# PX4FMUv2_4_6_8.net
KiCad netlist of a schematic drawn in Altium Designer
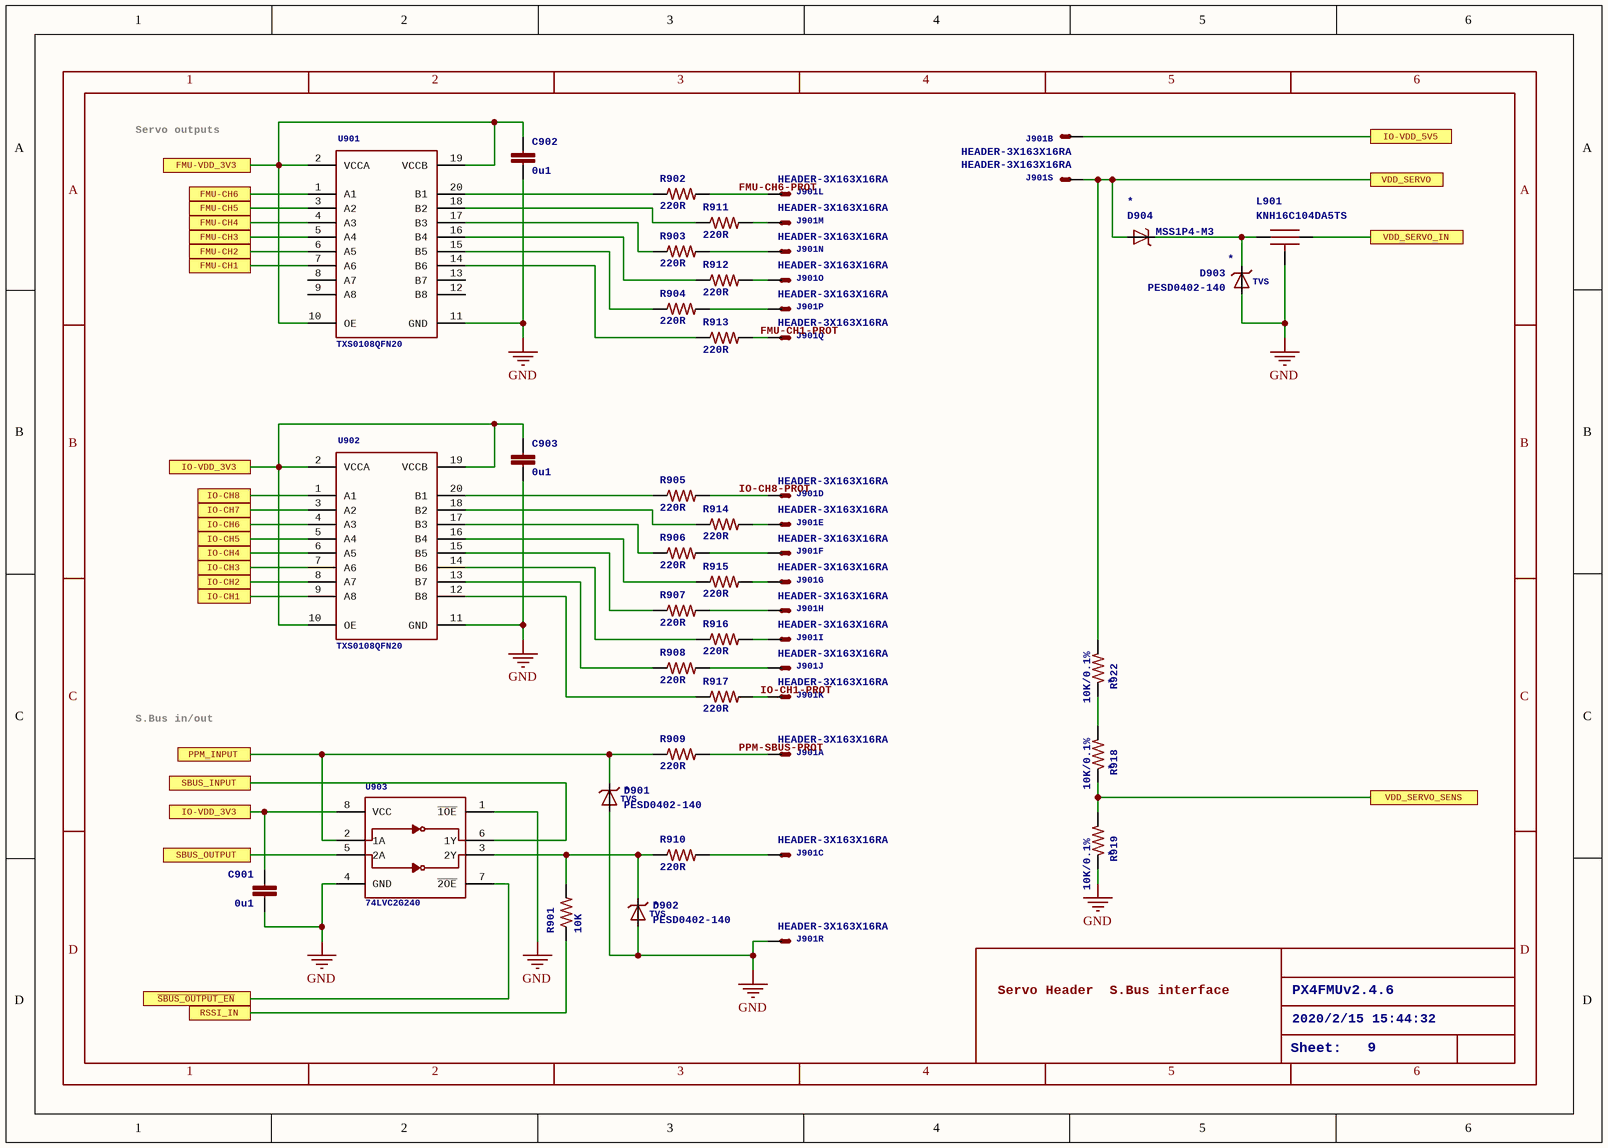
[diagram p0: PX4FMUv2.4.6_8.SchDoc]

(export (version "E")
  (design (tool "Eeschema 10.0.6"))
  (components
    (comp (ref "C901")
      (value "0u1")
      (footprint "0402-CAP")
      (description "CapacitorStandard 0603 ceramic capacitor, and 0.1\" leaded capacitor.")
      (fields (field (name "PARTNO") "CC0402ZRY5V7BB104"))
      (libsource (lib "") (part "CAP0402_1"))
    )
    (comp (ref "C902")
      (value "0u1")
      (footprint "0402-CAP")
      (description "CapacitorStandard 0603 ceramic capacitor, and 0.1\" leaded capacitor.")
      (fields (field (name "PARTNO") "CC0402ZRY5V7BB104"))
      (libsource (lib "pixhawk2") (part "CAP0402"))
    )
    (comp (ref "C903")
      (value "0u1")
      (footprint "0402-CAP")
      (description "CapacitorStandard 0603 ceramic capacitor, and 0.1\" leaded capacitor.")
      (fields (field (name "PARTNO") "CC0402ZRY5V7BB104"))
      (libsource (lib "pixhawk2") (part "CAP0402"))
    )
    (comp (ref "D901")
      (value "PESD0402-140")
      (footprint "0402-TVS")
      (fields (field (name "NAME") "*") (field (name "TVS") "TVS"))
      (libsource (lib "pixhawk2") (part "DIODE-TVS"))
    )
    (comp (ref "D902")
      (value "PESD0402-140")
      (footprint "0402-TVS")
      (fields (field (name "NAME") "*") (field (name "TVS") "TVS"))
      (libsource (lib "pixhawk2") (part "DIODE-TVS"))
    )
    (comp (ref "D903")
      (value "PESD0402-140")
      (footprint "0402-TVS")
      (fields (field (name "NAME") "*") (field (name "TVS") "TVS"))
      (libsource (lib "pixhawk2") (part "DIODE-TVS"))
    )
    (comp (ref "D904")
      (value "MSS1P4-M3")
      (footprint "MICROSMP")
      (description "Schottky barrier diode in DO214AC, e.g. Fairchild SS14.")
      (fields (field (name "NAME") "*") (field (name "PARTNO") "MSS1P4-M3/89A"))
      (libsource (lib "pixhawk2") (part "DIODE-SCHOTTKY_MSMP"))
    )
    (comp (ref "J901")
      (value "HEADER-3X163X16RA")
      (footprint "3X16RA")
      (description "3x16 servo header")
      (libsource (lib "pixhawk2") (part "HEADER-3X163X16RA"))
    )
    (comp (ref "L901")
      (value "KNH16C104DA5TS")
      (footprint "KYOCERA-KNH16-DA")
      (description "Kyocera KNH16C104DA5TS EMI filter")
      (libsource (lib "pixhawk2") (part "KNH16C104DA5TS"))
    )
    (comp (ref "R901")
      (value "10K")
      (footprint "0402-RES")
      (fields (field (name "PARTNO") "RC0402FR-0710KL"))
      (libsource (lib "pixhawk2") (part "RESISTOR0402-RES"))
    )
    (comp (ref "R902")
      (value "220R")
      (footprint "0402-RES")
      (fields (field (name "PARTNO") "RC0402FR-07220RL"))
      (libsource (lib "pixhawk2") (part "RESISTOR0402-RES"))
    )
    (comp (ref "R903")
      (value "220R")
      (footprint "0402-RES")
      (fields (field (name "PARTNO") "RC0402FR-07220RL"))
      (libsource (lib "pixhawk2") (part "RESISTOR0402-RES"))
    )
    (comp (ref "R904")
      (value "220R")
      (footprint "0402-RES")
      (fields (field (name "PARTNO") "RC0402FR-07220RL"))
      (libsource (lib "pixhawk2") (part "RESISTOR0402-RES"))
    )
    (comp (ref "R905")
      (value "220R")
      (footprint "0402-RES")
      (fields (field (name "PARTNO") "RC0402FR-07220RL"))
      (libsource (lib "pixhawk2") (part "RESISTOR0402-RES"))
    )
    (comp (ref "R906")
      (value "220R")
      (footprint "0402-RES")
      (fields (field (name "PARTNO") "RC0402FR-07220RL"))
      (libsource (lib "pixhawk2") (part "RESISTOR0402-RES"))
    )
    (comp (ref "R907")
      (value "220R")
      (footprint "0402-RES")
      (fields (field (name "PARTNO") "RC0402FR-07220RL"))
      (libsource (lib "pixhawk2") (part "RESISTOR0402-RES"))
    )
    (comp (ref "R908")
      (value "220R")
      (footprint "0402-RES")
      (fields (field (name "PARTNO") "RC0402FR-07220RL"))
      (libsource (lib "pixhawk2") (part "RESISTOR0402-RES"))
    )
    (comp (ref "R909")
      (value "220R")
      (footprint "0402-RES")
      (fields (field (name "PARTNO") "RC0402FR-07220RL"))
      (libsource (lib "pixhawk2") (part "RESISTOR0402-RES"))
    )
    (comp (ref "R910")
      (value "220R")
      (footprint "0402-RES")
      (fields (field (name "PARTNO") "RC0402FR-07220RL"))
      (libsource (lib "pixhawk2") (part "RESISTOR0402-RES"))
    )
    (comp (ref "R911")
      (value "220R")
      (footprint "0402-RES")
      (fields (field (name "PARTNO") "RC0402FR-07220RL"))
      (libsource (lib "pixhawk2") (part "RESISTOR0402-RES"))
    )
    (comp (ref "R912")
      (value "220R")
      (footprint "0402-RES")
      (fields (field (name "PARTNO") "RC0402FR-07220RL"))
      (libsource (lib "pixhawk2") (part "RESISTOR0402-RES"))
    )
    (comp (ref "R913")
      (value "220R")
      (footprint "0402-RES")
      (fields (field (name "PARTNO") "RC0402FR-07220RL"))
      (libsource (lib "pixhawk2") (part "RESISTOR0402-RES"))
    )
    (comp (ref "R914")
      (value "220R")
      (footprint "0402-RES")
      (fields (field (name "PARTNO") "RC0402FR-07220RL"))
      (libsource (lib "pixhawk2") (part "RESISTOR0402-RES"))
    )
    (comp (ref "R915")
      (value "220R")
      (footprint "0402-RES")
      (fields (field (name "PARTNO") "RC0402FR-07220RL"))
      (libsource (lib "pixhawk2") (part "RESISTOR0402-RES"))
    )
    (comp (ref "R916")
      (value "220R")
      (footprint "0402-RES")
      (fields (field (name "PARTNO") "RC0402FR-07220RL"))
      (libsource (lib "pixhawk2") (part "RESISTOR0402-RES"))
    )
    (comp (ref "R917")
      (value "220R")
      (footprint "0402-RES")
      (fields (field (name "PARTNO") "RC0402FR-07220RL"))
      (libsource (lib "pixhawk2") (part "RESISTOR0402-RES"))
    )
    (comp (ref "R918")
      (value "10K/0.1%")
      (footprint "0402-RES")
      (fields (field (name "NAME") "*") (field (name "PARTNO") "ERA-2AEB103X"))
      (libsource (lib "pixhawk2") (part "RESISTOR0402-RES"))
    )
    (comp (ref "R919")
      (value "10K/0.1%")
      (footprint "0402-RES")
      (fields (field (name "NAME") "*") (field (name "PARTNO") "ERA-2AEB103X"))
      (libsource (lib "pixhawk2") (part "RESISTOR0402-RES"))
    )
    (comp (ref "R922")
      (value "10K/0.1%")
      (footprint "0402-RES")
      (fields (field (name "NAME") "*") (field (name "PARTNO") "ERA-2AEB103X"))
      (libsource (lib "pixhawk2") (part "RESISTOR0402-RES"))
    )
    (comp (ref "U901")
      (value "TXS0108QFN20")
      (footprint "QFN20-RGY")
      (fields (field (name "PARTNO") "TXS0108ERGYR"))
      (libsource (lib "pixhawk2") (part "TXS0108QFN20"))
    )
    (comp (ref "U902")
      (value "TXS0108QFN20")
      (footprint "QFN20-RGY")
      (fields (field (name "PARTNO") "TXS0108ERGYR"))
      (libsource (lib "pixhawk2") (part "TXS0108QFN20"))
    )
    (comp (ref "U903")
      (value "74LVC2G240")
      (footprint "TSSOP8_SOT505-2")
      (fields (field (name "PARTNO") "74LVC2G240DP,125"))
      (libsource (lib "pixhawk2") (part "74LVC2G240-TSSOP-8"))
    )
  )
  (nets
    (net (code "1") (name "/FMU-CH1") (class "Default")
      (node (ref "U901") (pin "7") (pinfunction "A6_7") (pintype "passive"))
    )
    (net (code "2") (name "/FMU-CH1-PROT") (class "Default")
      (node (ref "J901") (pin "46") (pinfunction "S_46") (pintype "passive"))
      (node (ref "R913") (pin "P$2") (pinfunction "2_P$2") (pintype "passive"))
    )
    (net (code "3") (name "/FMU-CH2") (class "Default")
      (node (ref "U901") (pin "6") (pinfunction "A5_6") (pintype "passive"))
    )
    (net (code "4") (name "/FMU-CH3") (class "Default")
      (node (ref "U901") (pin "5") (pinfunction "A4_5") (pintype "passive"))
    )
    (net (code "5") (name "/FMU-CH4") (class "Default")
      (node (ref "U901") (pin "4") (pinfunction "A3_4") (pintype "passive"))
    )
    (net (code "6") (name "/FMU-CH5") (class "Default")
      (node (ref "U901") (pin "3") (pinfunction "A2_3") (pintype "passive"))
    )
    (net (code "7") (name "/FMU-CH6") (class "Default")
      (node (ref "U901") (pin "1") (pinfunction "A1_1") (pintype "passive"))
    )
    (net (code "8") (name "/FMU-CH6-PROT") (class "Default")
      (node (ref "J901") (pin "31") (pinfunction "S_31") (pintype "passive"))
      (node (ref "R902") (pin "P$2") (pinfunction "2_P$2") (pintype "passive"))
    )
    (net (code "9") (name "/FMU-VDD_3V3") (class "Default")
      (node (ref "C902") (pin "P$1") (pinfunction "1_P$1") (pintype "passive"))
      (node (ref "U901") (pin "10") (pinfunction "OE_10") (pintype "passive"))
      (node (ref "U901") (pin "19") (pinfunction "VCCB_19") (pintype "passive"))
      (node (ref "U901") (pin "2") (pinfunction "VCCA_2") (pintype "passive"))
    )
    (net (code "10") (name "/IO-CH1") (class "Default")
      (node (ref "U902") (pin "9") (pinfunction "A8_9") (pintype "passive"))
    )
    (net (code "11") (name "/IO-CH1-PROT") (class "Default")
      (node (ref "J901") (pin "28") (pinfunction "S_28") (pintype "passive"))
      (node (ref "R917") (pin "P$2") (pinfunction "2_P$2") (pintype "passive"))
    )
    (net (code "12") (name "/IO-CH2") (class "Default")
      (node (ref "U902") (pin "8") (pinfunction "A7_8") (pintype "passive"))
    )
    (net (code "13") (name "/IO-CH3") (class "Default")
      (node (ref "U902") (pin "7") (pinfunction "A6_7") (pintype "passive"))
    )
    (net (code "14") (name "/IO-CH4") (class "Default")
      (node (ref "U902") (pin "6") (pinfunction "A5_6") (pintype "passive"))
    )
    (net (code "15") (name "/IO-CH5") (class "Default")
      (node (ref "U902") (pin "5") (pinfunction "A4_5") (pintype "passive"))
    )
    (net (code "16") (name "/IO-CH6") (class "Default")
      (node (ref "U902") (pin "4") (pinfunction "A3_4") (pintype "passive"))
    )
    (net (code "17") (name "/IO-CH7") (class "Default")
      (node (ref "U902") (pin "3") (pinfunction "A2_3") (pintype "passive"))
    )
    (net (code "18") (name "/IO-CH8") (class "Default")
      (node (ref "U902") (pin "1") (pinfunction "A1_1") (pintype "passive"))
    )
    (net (code "19") (name "/IO-CH8-PROT") (class "Default")
      (node (ref "J901") (pin "7") (pinfunction "S_7") (pintype "passive"))
      (node (ref "R905") (pin "P$2") (pinfunction "2_P$2") (pintype "passive"))
    )
    (net (code "20") (name "/IO-VDD_3V3") (class "Default")
      (node (ref "C901") (pin "P$1") (pinfunction "1_P$1") (pintype "passive"))
      (node (ref "C903") (pin "P$1") (pinfunction "1_P$1") (pintype "passive"))
      (node (ref "U902") (pin "10") (pinfunction "OE_10") (pintype "passive"))
      (node (ref "U902") (pin "19") (pinfunction "VCCB_19") (pintype "passive"))
      (node (ref "U902") (pin "2") (pinfunction "VCCA_2") (pintype "passive"))
      (node (ref "U903") (pin "8") (pinfunction "VCC_8") (pintype "open_emitter"))
    )
    (net (code "21") (name "/IO-VDD_5V5") (class "Default")
      (node (ref "J901") (pin "2") (pinfunction "S_2") (pintype "passive"))
    )
    (net (code "22") (name "/PPM-SBUS-PROT") (class "Default")
      (node (ref "J901") (pin "1") (pinfunction "S_1") (pintype "passive"))
      (node (ref "R909") (pin "P$2") (pinfunction "2_P$2") (pintype "passive"))
    )
    (net (code "23") (name "/PPM_INPUT") (class "Default")
      (node (ref "D901") (pin "C") (pinfunction "C_C") (pintype "passive"))
      (node (ref "R909") (pin "P$1") (pinfunction "1_P$1") (pintype "passive"))
      (node (ref "U903") (pin "2") (pinfunction "1A_2") (pintype "passive"))
    )
    (net (code "24") (name "/RSSI_IN") (class "Default")
      (node (ref "R901") (pin "P$1") (pinfunction "1_P$1") (pintype "passive"))
    )
    (net (code "25") (name "/SBUS_INPUT") (class "Default")
      (node (ref "U903") (pin "6") (pinfunction "1Y_6") (pintype "passive"))
    )
    (net (code "26") (name "/SBUS_OUTPUT") (class "Default")
      (node (ref "U903") (pin "5") (pinfunction "2A_5") (pintype "passive"))
    )
    (net (code "27") (name "/VDD_SERVO") (class "Default")
      (node (ref "D904") (pin "ANODE") (pinfunction "A_ANODE") (pintype "passive"))
      (node (ref "J901") (pin "5_8_11_14_17_20_23_26_29_32_35_38_41_44_47") (pinfunction "S_5_8_11_14_17_20_23_26_29_32_35_38_41_44_47") (pintype "passive"))
      (node (ref "R922") (pin "P$2") (pinfunction "2_P$2") (pintype "passive"))
    )
    (net (code "28") (name "/VDD_SERVO_IN") (class "Default")
      (node (ref "L901") (pin "P$2") (pinfunction "P$2_P$2") (pintype "passive"))
    )
    (net (code "29") (name "/VDD_SERVO_SENS") (class "Default")
      (node (ref "R918") (pin "P$1") (pinfunction "1_P$1") (pintype "passive"))
      (node (ref "R919") (pin "P$2") (pinfunction "2_P$2") (pintype "passive"))
    )
    (net (code "30") (name "/~{SBUS_OUTPUT_EN}") (class "Default")
      (node (ref "U903") (pin "7") (pinfunction "~{2OE}_7") (pintype "passive"))
    )
    (net (code "31") (name "GND") (class "Default")
      (node (ref "C901") (pin "P$2") (pinfunction "2_P$2") (pintype "passive"))
      (node (ref "C902") (pin "P$2") (pinfunction "2_P$2") (pintype "passive"))
      (node (ref "C903") (pin "P$2") (pinfunction "2_P$2") (pintype "passive"))
      (node (ref "D901") (pin "A") (pinfunction "A_A") (pintype "passive"))
      (node (ref "D902") (pin "A") (pinfunction "A_A") (pintype "passive"))
      (node (ref "D903") (pin "A") (pinfunction "A_A") (pintype "passive"))
      (node (ref "J901") (pin "3_6_9_12_15_18_21_24_27_30_33_36_39_42_45_48") (pinfunction "S_3_6_9_12_15_18_21_24_27_30_33_36_39_42_45_48") (pintype "passive"))
      (node (ref "L901") (pin "P$3_P$4_P$5") (pinfunction "P$3_P$3_P$4_P$5") (pintype "passive"))
      (node (ref "R919") (pin "P$1") (pinfunction "1_P$1") (pintype "passive"))
      (node (ref "U901") (pin "11") (pinfunction "GND_11") (pintype "open_emitter"))
      (node (ref "U902") (pin "11") (pinfunction "GND_11") (pintype "open_emitter"))
      (node (ref "U903") (pin "1") (pinfunction "~{1OE}_1") (pintype "passive"))
      (node (ref "U903") (pin "4") (pinfunction "GND_4") (pintype "open_emitter"))
    )
    (net (code "32") (name "Net-(D904-C)") (class "Default")
      (node (ref "D903") (pin "C") (pinfunction "C_C") (pintype "passive"))
      (node (ref "D904") (pin "CATHODE") (pinfunction "C_CATHODE") (pintype "passive"))
      (node (ref "L901") (pin "P$1") (pinfunction "P$1_P$1") (pintype "passive"))
    )
    (net (code "33") (name "Net-(J901C-S)") (class "Default")
      (node (ref "J901") (pin "4") (pinfunction "S_4") (pintype "passive"))
      (node (ref "R910") (pin "P$2") (pinfunction "2_P$2") (pintype "passive"))
    )
    (net (code "34") (name "Net-(J901E-S)") (class "Default")
      (node (ref "J901") (pin "10") (pinfunction "S_10") (pintype "passive"))
      (node (ref "R914") (pin "P$2") (pinfunction "2_P$2") (pintype "passive"))
    )
    (net (code "35") (name "Net-(J901F-S)") (class "Default")
      (node (ref "J901") (pin "13") (pinfunction "S_13") (pintype "passive"))
      (node (ref "R906") (pin "P$2") (pinfunction "2_P$2") (pintype "passive"))
    )
    (net (code "36") (name "Net-(J901G-S)") (class "Default")
      (node (ref "J901") (pin "16") (pinfunction "S_16") (pintype "passive"))
      (node (ref "R915") (pin "P$2") (pinfunction "2_P$2") (pintype "passive"))
    )
    (net (code "37") (name "Net-(J901H-S)") (class "Default")
      (node (ref "J901") (pin "19") (pinfunction "S_19") (pintype "passive"))
      (node (ref "R907") (pin "P$2") (pinfunction "2_P$2") (pintype "passive"))
    )
    (net (code "38") (name "Net-(J901I-S)") (class "Default")
      (node (ref "J901") (pin "22") (pinfunction "S_22") (pintype "passive"))
      (node (ref "R916") (pin "P$2") (pinfunction "2_P$2") (pintype "passive"))
    )
    (net (code "39") (name "Net-(J901J-S)") (class "Default")
      (node (ref "J901") (pin "25") (pinfunction "S_25") (pintype "passive"))
      (node (ref "R908") (pin "P$2") (pinfunction "2_P$2") (pintype "passive"))
    )
    (net (code "40") (name "Net-(J901M-S)") (class "Default")
      (node (ref "J901") (pin "34") (pinfunction "S_34") (pintype "passive"))
      (node (ref "R911") (pin "P$2") (pinfunction "2_P$2") (pintype "passive"))
    )
    (net (code "41") (name "Net-(J901N-S)") (class "Default")
      (node (ref "J901") (pin "37") (pinfunction "S_37") (pintype "passive"))
      (node (ref "R903") (pin "P$2") (pinfunction "2_P$2") (pintype "passive"))
    )
    (net (code "42") (name "Net-(J901O-S)") (class "Default")
      (node (ref "J901") (pin "40") (pinfunction "S_40") (pintype "passive"))
      (node (ref "R912") (pin "P$2") (pinfunction "2_P$2") (pintype "passive"))
    )
    (net (code "43") (name "Net-(J901P-S)") (class "Default")
      (node (ref "J901") (pin "43") (pinfunction "S_43") (pintype "passive"))
      (node (ref "R904") (pin "P$2") (pinfunction "2_P$2") (pintype "passive"))
    )
    (net (code "44") (name "Net-(R901-2)") (class "Default")
      (node (ref "D902") (pin "C") (pinfunction "C_C") (pintype "passive"))
      (node (ref "R901") (pin "P$2") (pinfunction "2_P$2") (pintype "passive"))
      (node (ref "R910") (pin "P$1") (pinfunction "1_P$1") (pintype "passive"))
      (node (ref "U903") (pin "3") (pinfunction "2Y_3") (pintype "passive"))
    )
    (net (code "45") (name "Net-(R902-1)") (class "Default")
      (node (ref "R902") (pin "P$1") (pinfunction "1_P$1") (pintype "passive"))
      (node (ref "U901") (pin "20") (pinfunction "B1_20") (pintype "passive"))
    )
    (net (code "46") (name "Net-(R903-1)") (class "Default")
      (node (ref "R903") (pin "P$1") (pinfunction "1_P$1") (pintype "passive"))
      (node (ref "U901") (pin "17") (pinfunction "B3_17") (pintype "passive"))
    )
    (net (code "47") (name "Net-(R904-1)") (class "Default")
      (node (ref "R904") (pin "P$1") (pinfunction "1_P$1") (pintype "passive"))
      (node (ref "U901") (pin "15") (pinfunction "B5_15") (pintype "passive"))
    )
    (net (code "48") (name "Net-(R905-1)") (class "Default")
      (node (ref "R905") (pin "P$1") (pinfunction "1_P$1") (pintype "passive"))
      (node (ref "U902") (pin "20") (pinfunction "B1_20") (pintype "passive"))
    )
    (net (code "49") (name "Net-(R906-1)") (class "Default")
      (node (ref "R906") (pin "P$1") (pinfunction "1_P$1") (pintype "passive"))
      (node (ref "U902") (pin "17") (pinfunction "B3_17") (pintype "passive"))
    )
    (net (code "50") (name "Net-(R907-1)") (class "Default")
      (node (ref "R907") (pin "P$1") (pinfunction "1_P$1") (pintype "passive"))
      (node (ref "U902") (pin "15") (pinfunction "B5_15") (pintype "passive"))
    )
    (net (code "51") (name "Net-(R908-1)") (class "Default")
      (node (ref "R908") (pin "P$1") (pinfunction "1_P$1") (pintype "passive"))
      (node (ref "U902") (pin "13") (pinfunction "B7_13") (pintype "passive"))
    )
    (net (code "52") (name "Net-(R911-1)") (class "Default")
      (node (ref "R911") (pin "P$1") (pinfunction "1_P$1") (pintype "passive"))
      (node (ref "U901") (pin "18") (pinfunction "B2_18") (pintype "passive"))
    )
    (net (code "53") (name "Net-(R912-1)") (class "Default")
      (node (ref "R912") (pin "P$1") (pinfunction "1_P$1") (pintype "passive"))
      (node (ref "U901") (pin "16") (pinfunction "B4_16") (pintype "passive"))
    )
    (net (code "54") (name "Net-(R913-1)") (class "Default")
      (node (ref "R913") (pin "P$1") (pinfunction "1_P$1") (pintype "passive"))
      (node (ref "U901") (pin "14") (pinfunction "B6_14") (pintype "passive"))
    )
    (net (code "55") (name "Net-(R914-1)") (class "Default")
      (node (ref "R914") (pin "P$1") (pinfunction "1_P$1") (pintype "passive"))
      (node (ref "U902") (pin "18") (pinfunction "B2_18") (pintype "passive"))
    )
    (net (code "56") (name "Net-(R915-1)") (class "Default")
      (node (ref "R915") (pin "P$1") (pinfunction "1_P$1") (pintype "passive"))
      (node (ref "U902") (pin "16") (pinfunction "B4_16") (pintype "passive"))
    )
    (net (code "57") (name "Net-(R916-1)") (class "Default")
      (node (ref "R916") (pin "P$1") (pinfunction "1_P$1") (pintype "passive"))
      (node (ref "U902") (pin "14") (pinfunction "B6_14") (pintype "passive"))
    )
    (net (code "58") (name "Net-(R917-1)") (class "Default")
      (node (ref "R917") (pin "P$1") (pinfunction "1_P$1") (pintype "passive"))
      (node (ref "U902") (pin "12") (pinfunction "B8_12") (pintype "passive"))
    )
    (net (code "59") (name "Net-(R918-2)") (class "Default")
      (node (ref "R918") (pin "P$2") (pinfunction "2_P$2") (pintype "passive"))
      (node (ref "R922") (pin "P$1") (pinfunction "1_P$1") (pintype "passive"))
    )
    (net (code "60") (name "unconnected-(U901-A7-Pad8)") (class "Default")
      (node (ref "U901") (pin "8") (pinfunction "A7_8") (pintype "passive"))
    )
    (net (code "61") (name "unconnected-(U901-A8-Pad9)") (class "Default")
      (node (ref "U901") (pin "9") (pinfunction "A8_9") (pintype "passive"))
    )
    (net (code "62") (name "unconnected-(U901-B7-Pad13)") (class "Default")
      (node (ref "U901") (pin "13") (pinfunction "B7_13") (pintype "passive"))
    )
    (net (code "63") (name "unconnected-(U901-B8-Pad12)") (class "Default")
      (node (ref "U901") (pin "12") (pinfunction "B8_12") (pintype "passive"))
    )
  )
)
